# BMS.net
KiCad netlist of a schematic drawn in Altium Designer
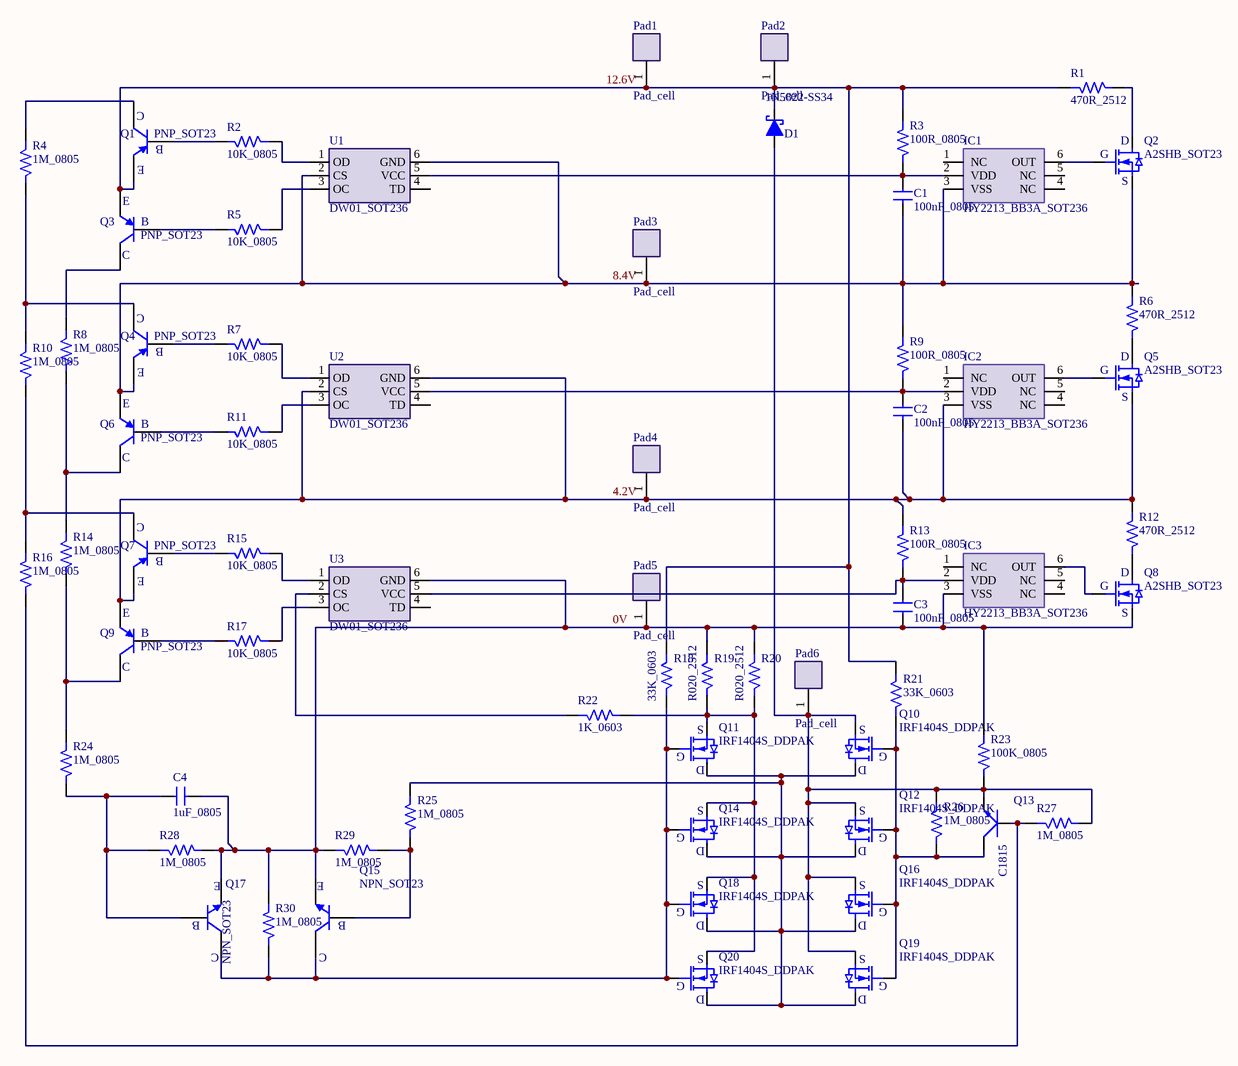
[diagram p0: BMS.SchDoc]

(export (version "E")
  (design (tool "Eeschema 10.0.6"))
  (components
    (comp (ref "C1")
      (value "100nF_0805")
      (footprint "CN-SMD-0805 - H32")
      (description "Cap SMD, 0.08x0.05 inch, 2.0x1.2 mm - 2012")
      (libsource (lib "LYAM_LIB") (part "CAP 0805 104"))
    )
    (comp (ref "C2")
      (value "100nF_0805")
      (footprint "CN-SMD-0805 - H32")
      (description "Cap SMD, 0.08x0.05 inch, 2.0x1.2 mm - 2012")
      (libsource (lib "LYAM_LIB") (part "CAP 0805 104"))
    )
    (comp (ref "C3")
      (value "100nF_0805")
      (footprint "CN-SMD-0805 - H32")
      (description "Cap SMD, 0.08x0.05 inch, 2.0x1.2 mm - 2012")
      (libsource (lib "LYAM_LIB") (part "CAP 0805 104"))
    )
    (comp (ref "C4")
      (value "1uF_0805")
      (footprint "CN-SMD-0805 - H50")
      (description "Cap SMD, 0.08x0.05 inch, 2.0x1.2 mm - 2012")
      (libsource (lib "LYAM_LIB") (part "CAP 0805 105"))
    )
    (comp (ref "D1")
      (value "1N5822-SS34")
      (footprint "SMA")
      (description "Schottky diode, 3A, VRRM 40V")
      (fields (field (name "PUBLISHER") "Altium Limited"))
      (libsource (lib "LYAM_LIB") (part "Diode 1N5822 SS34"))
    )
    (comp (ref "IC1")
      (value "HY2213_BB3A_SOT236")
      (footprint "SOT23-6")
      (description "1  Cell  Li-ion/Polymer  Battery  Charge  Balance  IC")
      (libsource (lib "LYAM_LIB") (part "HY2213"))
    )
    (comp (ref "IC2")
      (value "HY2213_BB3A_SOT236")
      (footprint "SOT23-6")
      (description "1  Cell  Li-ion/Polymer  Battery  Charge  Balance  IC")
      (libsource (lib "LYAM_LIB") (part "HY2213"))
    )
    (comp (ref "IC3")
      (value "HY2213_BB3A_SOT236")
      (footprint "SOT23-6")
      (description "1  Cell  Li-ion/Polymer  Battery  Charge  Balance  IC")
      (libsource (lib "LYAM_LIB") (part "HY2213"))
    )
    (comp (ref "Pad1")
      (value "Pad_cell")
      (footprint "Pad_cell")
      (libsource (lib "LYAM_LIB") (part "Pad_cell"))
    )
    (comp (ref "Pad2")
      (value "Pad_cell")
      (footprint "Pad_cell")
      (libsource (lib "LYAM_LIB") (part "Pad_cell"))
    )
    (comp (ref "Pad3")
      (value "Pad_cell")
      (footprint "Pad_cell")
      (libsource (lib "LYAM_LIB") (part "Pad_cell"))
    )
    (comp (ref "Pad4")
      (value "Pad_cell")
      (footprint "Pad_cell")
      (libsource (lib "LYAM_LIB") (part "Pad_cell"))
    )
    (comp (ref "Pad5")
      (value "Pad_cell")
      (footprint "Pad_cell")
      (libsource (lib "LYAM_LIB") (part "Pad_cell"))
    )
    (comp (ref "Pad6")
      (value "Pad_cell")
      (footprint "Pad_cell")
      (libsource (lib "LYAM_LIB") (part "Pad_cell"))
    )
    (comp (ref "Q1")
      (value "PNP_SOT23")
      (footprint "SOT23_3")
      (description "Transistor SMD MMBT5401 PNP 150V - SOT23")
      (libsource (lib "LYAM_LIB") (part "MMBT5401"))
    )
    (comp (ref "Q2")
      (value "A2SHB_SOT23")
      (footprint "SOT-23-3L")
      (description "N-Channel\r\nEnhancement Mode\r\nField Effect Transistor")
      (libsource (lib "LYAM_LIB") (part "HNM2302ALB"))
    )
    (comp (ref "Q3")
      (value "PNP_SOT23")
      (footprint "SOT23_3")
      (description "Transistor SMD MMBT5401 PNP 150V - SOT23")
      (libsource (lib "LYAM_LIB") (part "MMBT5401"))
    )
    (comp (ref "Q4")
      (value "PNP_SOT23")
      (footprint "SOT23_3")
      (description "Transistor SMD MMBT5401 PNP 150V - SOT23")
      (libsource (lib "LYAM_LIB") (part "MMBT5401"))
    )
    (comp (ref "Q5")
      (value "A2SHB_SOT23")
      (footprint "SOT-23-3L")
      (description "N-Channel\r\nEnhancement Mode\r\nField Effect Transistor")
      (libsource (lib "LYAM_LIB") (part "HNM2302ALB"))
    )
    (comp (ref "Q6")
      (value "PNP_SOT23")
      (footprint "SOT23_3")
      (description "Transistor SMD MMBT5401 PNP 150V - SOT23")
      (libsource (lib "LYAM_LIB") (part "MMBT5401"))
    )
    (comp (ref "Q7")
      (value "PNP_SOT23")
      (footprint "SOT23_3")
      (description "Transistor SMD MMBT5401 PNP 150V - SOT23")
      (libsource (lib "LYAM_LIB") (part "MMBT5401"))
    )
    (comp (ref "Q8")
      (value "A2SHB_SOT23")
      (footprint "SOT-23-3L")
      (description "N-Channel\r\nEnhancement Mode\r\nField Effect Transistor")
      (libsource (lib "LYAM_LIB") (part "HNM2302ALB"))
    )
    (comp (ref "Q9")
      (value "PNP_SOT23")
      (footprint "SOT23_3")
      (description "Transistor SMD MMBT5401 PNP 150V - SOT23")
      (libsource (lib "LYAM_LIB") (part "MMBT5401"))
    )
    (comp (ref "Q10")
      (value "IRF1404S_DDPAK")
      (footprint "TO263-3_DDPAK")
      (description "IRF1404S TO263 MOSFET N-CH 162A 40V")
      (libsource (lib "LYAM_LIB") (part "IRF1404S"))
    )
    (comp (ref "Q11")
      (value "IRF1404S_DDPAK")
      (footprint "TO263-3_DDPAK")
      (description "IRF1404S TO263 MOSFET N-CH 162A 40V")
      (libsource (lib "LYAM_LIB") (part "IRF1404S"))
    )
    (comp (ref "Q12")
      (value "IRF1404S_DDPAK")
      (footprint "TO263-3_DDPAK")
      (description "IRF1404S TO263 MOSFET N-CH 162A 40V")
      (libsource (lib "LYAM_LIB") (part "IRF1404S"))
    )
    (comp (ref "Q13")
      (value "C1815")
      (footprint "SOT23B")
      (description "NPN 600mW, ECB")
      (libsource (lib "LYAM_LIB") (part "Transistor C1815"))
    )
    (comp (ref "Q14")
      (value "IRF1404S_DDPAK")
      (footprint "TO263-3_DDPAK")
      (description "IRF1404S TO263 MOSFET N-CH 162A 40V")
      (libsource (lib "LYAM_LIB") (part "IRF1404S"))
    )
    (comp (ref "Q15")
      (value "NPN_SOT23")
      (footprint "SOT23_3")
      (description "2N5551 MMBT5551 G1 NPN Transistor 0.6A 160V SOT-23")
      (libsource (lib "LYAM_LIB") (part "MMBT5551"))
    )
    (comp (ref "Q16")
      (value "IRF1404S_DDPAK")
      (footprint "TO263-3_DDPAK")
      (description "IRF1404S TO263 MOSFET N-CH 162A 40V")
      (libsource (lib "LYAM_LIB") (part "IRF1404S"))
    )
    (comp (ref "Q17")
      (value "NPN_SOT23")
      (footprint "SOT23_3")
      (description "2N5551 MMBT5551 G1 NPN Transistor 0.6A 160V SOT-23")
      (libsource (lib "LYAM_LIB") (part "MMBT5551"))
    )
    (comp (ref "Q18")
      (value "IRF1404S_DDPAK")
      (footprint "TO263-3_DDPAK")
      (description "IRF1404S TO263 MOSFET N-CH 162A 40V")
      (libsource (lib "LYAM_LIB") (part "IRF1404S"))
    )
    (comp (ref "Q19")
      (value "IRF1404S_DDPAK")
      (footprint "TO263-3_DDPAK")
      (description "IRF1404S TO263 MOSFET N-CH 162A 40V")
      (libsource (lib "LYAM_LIB") (part "IRF1404S"))
    )
    (comp (ref "Q20")
      (value "IRF1404S_DDPAK")
      (footprint "TO263-3_DDPAK")
      (description "IRF1404S TO263 MOSFET N-CH 162A 40V")
      (libsource (lib "LYAM_LIB") (part "IRF1404S"))
    )
    (comp (ref "R1")
      (value "470R_2512")
      (footprint "RES-SMD-2512")
      (description "Resistor SMD, 0.25x0.12 inch, 6.3x3.2 mm - 6332, 1W")
      (libsource (lib "LYAM_LIB") (part "RES 2512 470R"))
    )
    (comp (ref "R2")
      (value "10K_0805")
      (footprint "RES-SMD-0805")
      (description "Resistor SMD, 0.08x0.05 inch, 2.0x1.2 mm - 2012, 1/8W")
      (libsource (lib "LYAM_LIB") (part "RES 0805 10K"))
    )
    (comp (ref "R3")
      (value "100R_0805")
      (footprint "RES-SMD-0805")
      (description "Resistor SMD, 0.08x0.05 inch, 2.0x1.2 mm - 2012, 1/8W")
      (libsource (lib "LYAM_LIB") (part "RES 0805 100R"))
    )
    (comp (ref "R4")
      (value "1M_0805")
      (footprint "RES-SMD-0805")
      (description "Resistor SMD, 0.08x0.05 inch, 2.0x1.2 mm - 2012, 1/8W")
      (libsource (lib "LYAM_LIB") (part "RES 0805 1M"))
    )
    (comp (ref "R5")
      (value "10K_0805")
      (footprint "RES-SMD-0805")
      (description "Resistor SMD, 0.08x0.05 inch, 2.0x1.2 mm - 2012, 1/8W")
      (libsource (lib "LYAM_LIB") (part "RES 0805 10K"))
    )
    (comp (ref "R6")
      (value "470R_2512")
      (footprint "RES-SMD-2512")
      (description "Resistor SMD, 0.25x0.12 inch, 6.3x3.2 mm - 6332, 1W")
      (libsource (lib "LYAM_LIB") (part "RES 2512 470R"))
    )
    (comp (ref "R7")
      (value "10K_0805")
      (footprint "RES-SMD-0805")
      (description "Resistor SMD, 0.08x0.05 inch, 2.0x1.2 mm - 2012, 1/8W")
      (libsource (lib "LYAM_LIB") (part "RES 0805 10K"))
    )
    (comp (ref "R8")
      (value "1M_0805")
      (footprint "RES-SMD-0805")
      (description "Resistor SMD, 0.08x0.05 inch, 2.0x1.2 mm - 2012, 1/8W")
      (libsource (lib "LYAM_LIB") (part "RES 0805 1M"))
    )
    (comp (ref "R9")
      (value "100R_0805")
      (footprint "RES-SMD-0805")
      (description "Resistor SMD, 0.08x0.05 inch, 2.0x1.2 mm - 2012, 1/8W")
      (libsource (lib "LYAM_LIB") (part "RES 0805 100R"))
    )
    (comp (ref "R10")
      (value "1M_0805")
      (footprint "RES-SMD-0805")
      (description "Resistor SMD, 0.08x0.05 inch, 2.0x1.2 mm - 2012, 1/8W")
      (libsource (lib "LYAM_LIB") (part "RES 0805 1M"))
    )
    (comp (ref "R11")
      (value "10K_0805")
      (footprint "RES-SMD-0805")
      (description "Resistor SMD, 0.08x0.05 inch, 2.0x1.2 mm - 2012, 1/8W")
      (libsource (lib "LYAM_LIB") (part "RES 0805 10K"))
    )
    (comp (ref "R12")
      (value "470R_2512")
      (footprint "RES-SMD-2512")
      (description "Resistor SMD, 0.25x0.12 inch, 6.3x3.2 mm - 6332, 1W")
      (libsource (lib "LYAM_LIB") (part "RES 2512 470R"))
    )
    (comp (ref "R13")
      (value "100R_0805")
      (footprint "RES-SMD-0805")
      (description "Resistor SMD, 0.08x0.05 inch, 2.0x1.2 mm - 2012, 1/8W")
      (libsource (lib "LYAM_LIB") (part "RES 0805 100R"))
    )
    (comp (ref "R14")
      (value "1M_0805")
      (footprint "RES-SMD-0805")
      (description "Resistor SMD, 0.08x0.05 inch, 2.0x1.2 mm - 2012, 1/8W")
      (libsource (lib "LYAM_LIB") (part "RES 0805 1M"))
    )
    (comp (ref "R15")
      (value "10K_0805")
      (footprint "RES-SMD-0805")
      (description "Resistor SMD, 0.08x0.05 inch, 2.0x1.2 mm - 2012, 1/8W")
      (libsource (lib "LYAM_LIB") (part "RES 0805 10K"))
    )
    (comp (ref "R16")
      (value "1M_0805")
      (footprint "RES-SMD-0805")
      (description "Resistor SMD, 0.08x0.05 inch, 2.0x1.2 mm - 2012, 1/8W")
      (libsource (lib "LYAM_LIB") (part "RES 0805 1M"))
    )
    (comp (ref "R17")
      (value "10K_0805")
      (footprint "RES-SMD-0805")
      (description "Resistor SMD, 0.08x0.05 inch, 2.0x1.2 mm - 2012, 1/8W")
      (libsource (lib "LYAM_LIB") (part "RES 0805 10K"))
    )
    (comp (ref "R18")
      (value "33K_0603")
      (footprint "RES-SMD-0603")
      (description "Resistor SMD, 0.06x0.03 inch, 1.55x0.85 mm - 1608, 1/10W")
      (libsource (lib "LYAM_LIB") (part "RES 0603 33K"))
    )
    (comp (ref "R19")
      (value "R020_2512")
      (footprint "RES-SMD-2512")
      (description "Resistor SMD, 0.25x0.12 inch, 6.3x3.2 mm - 6332, 1W")
      (libsource (lib "LYAM_LIB") (part "RES 2512 0.02R"))
    )
    (comp (ref "R20")
      (value "R020_2512")
      (footprint "RES-SMD-2512")
      (description "Resistor SMD, 0.25x0.12 inch, 6.3x3.2 mm - 6332, 1W")
      (libsource (lib "LYAM_LIB") (part "RES 2512 0.02R"))
    )
    (comp (ref "R21")
      (value "33K_0603")
      (footprint "RES-SMD-0603")
      (description "Resistor SMD, 0.06x0.03 inch, 1.55x0.85 mm - 1608, 1/10W")
      (libsource (lib "LYAM_LIB") (part "RES 0603 33K"))
    )
    (comp (ref "R22")
      (value "1K_0603")
      (footprint "RES-SMD-0603")
      (description "Resistor SMD, 0.06x0.03 inch, 1.55x0.85 mm - 1608, 1/10W")
      (libsource (lib "LYAM_LIB") (part "RES 0603 1K"))
    )
    (comp (ref "R23")
      (value "100K_0805")
      (footprint "RES-SMD-0805")
      (description "Resistor SMD, 0.08x0.05 inch, 2.0x1.2 mm - 2012, 1/8W")
      (libsource (lib "LYAM_LIB") (part "RES 0805 100K"))
    )
    (comp (ref "R24")
      (value "1M_0805")
      (footprint "RES-SMD-0805")
      (description "Resistor SMD, 0.08x0.05 inch, 2.0x1.2 mm - 2012, 1/8W")
      (libsource (lib "LYAM_LIB") (part "RES 0805 1M"))
    )
    (comp (ref "R25")
      (value "1M_0805")
      (footprint "RES-SMD-0805")
      (description "Resistor SMD, 0.08x0.05 inch, 2.0x1.2 mm - 2012, 1/8W")
      (libsource (lib "LYAM_LIB") (part "RES 0805 1M"))
    )
    (comp (ref "R26")
      (value "1M_0805")
      (footprint "RES-SMD-0805")
      (description "Resistor SMD, 0.08x0.05 inch, 2.0x1.2 mm - 2012, 1/8W")
      (libsource (lib "LYAM_LIB") (part "RES 0805 1M"))
    )
    (comp (ref "R27")
      (value "1M_0805")
      (footprint "RES-SMD-0805")
      (description "Resistor SMD, 0.08x0.05 inch, 2.0x1.2 mm - 2012, 1/8W")
      (libsource (lib "LYAM_LIB") (part "RES 0805 1M"))
    )
    (comp (ref "R28")
      (value "1M_0805")
      (footprint "RES-SMD-0805")
      (description "Resistor SMD, 0.08x0.05 inch, 2.0x1.2 mm - 2012, 1/8W")
      (libsource (lib "LYAM_LIB") (part "RES 0805 1M"))
    )
    (comp (ref "R29")
      (value "1M_0805")
      (footprint "RES-SMD-0805")
      (description "Resistor SMD, 0.08x0.05 inch, 2.0x1.2 mm - 2012, 1/8W")
      (libsource (lib "LYAM_LIB") (part "RES 0805 1M"))
    )
    (comp (ref "R30")
      (value "1M_0805")
      (footprint "RES-SMD-0805")
      (description "Resistor SMD, 0.08x0.05 inch, 2.0x1.2 mm - 2012, 1/8W")
      (libsource (lib "LYAM_LIB") (part "RES 0805 1M"))
    )
    (comp (ref "U1")
      (value "DW01_SOT236")
      (footprint "SOT23-6")
      (description "One Cell Lithium-ion/Polymer Battery Protection IC")
      (libsource (lib "LYAM_LIB") (part "DW01"))
    )
    (comp (ref "U2")
      (value "DW01_SOT236")
      (footprint "SOT23-6")
      (description "One Cell Lithium-ion/Polymer Battery Protection IC")
      (libsource (lib "LYAM_LIB") (part "DW01"))
    )
    (comp (ref "U3")
      (value "DW01_SOT236")
      (footprint "SOT23-6")
      (description "One Cell Lithium-ion/Polymer Battery Protection IC")
      (libsource (lib "LYAM_LIB") (part "DW01"))
    )
  )
  (nets
    (net (code "1") (name "/0V") (class "Default")
      (node (ref "C3") (pin "1") (pinfunction "1_1") (pintype "passive"))
      (node (ref "C4") (pin "2") (pinfunction "2_2") (pintype "passive"))
      (node (ref "IC3") (pin "3") (pinfunction "VSS_3") (pintype "passive"))
      (node (ref "Pad5") (pin "1") (pinfunction "11_1") (pintype "passive"))
      (node (ref "Q15") (pin "2") (pinfunction "E_2") (pintype "passive"))
      (node (ref "Q17") (pin "2") (pinfunction "E_2") (pintype "passive"))
      (node (ref "Q8") (pin "3") (pinfunction "S_3") (pintype "passive"))
      (node (ref "R19") (pin "2") (pinfunction "2_2") (pintype "passive"))
      (node (ref "R20") (pin "2") (pinfunction "2_2") (pintype "passive"))
      (node (ref "R23") (pin "2") (pinfunction "2_2") (pintype "passive"))
      (node (ref "R28") (pin "1") (pinfunction "1_1") (pintype "passive"))
      (node (ref "R29") (pin "2") (pinfunction "2_2") (pintype "passive"))
      (node (ref "R30") (pin "2") (pinfunction "2_2") (pintype "passive"))
      (node (ref "U3") (pin "6") (pinfunction "GND_6") (pintype "passive"))
    )
    (net (code "2") (name "/4.2V") (class "Default")
      (node (ref "C2") (pin "1") (pinfunction "1_1") (pintype "passive"))
      (node (ref "IC2") (pin "3") (pinfunction "VSS_3") (pintype "passive"))
      (node (ref "Pad4") (pin "1") (pinfunction "11_1") (pintype "passive"))
      (node (ref "Q5") (pin "3") (pinfunction "S_3") (pintype "passive"))
      (node (ref "Q7") (pin "2") (pinfunction "E_2") (pintype "passive"))
      (node (ref "Q9") (pin "2") (pinfunction "E_2") (pintype "passive"))
      (node (ref "R12") (pin "2") (pinfunction "2_2") (pintype "passive"))
      (node (ref "R13") (pin "2") (pinfunction "2_2") (pintype "passive"))
      (node (ref "U2") (pin "2") (pinfunction "CS_2") (pintype "passive"))
      (node (ref "U2") (pin "6") (pinfunction "GND_6") (pintype "passive"))
    )
    (net (code "3") (name "/8.4V") (class "Default")
      (node (ref "C1") (pin "1") (pinfunction "1_1") (pintype "passive"))
      (node (ref "IC1") (pin "3") (pinfunction "VSS_3") (pintype "passive"))
      (node (ref "Pad3") (pin "1") (pinfunction "11_1") (pintype "passive"))
      (node (ref "Q2") (pin "3") (pinfunction "S_3") (pintype "passive"))
      (node (ref "Q4") (pin "2") (pinfunction "E_2") (pintype "passive"))
      (node (ref "Q6") (pin "2") (pinfunction "E_2") (pintype "passive"))
      (node (ref "R6") (pin "2") (pinfunction "2_2") (pintype "passive"))
      (node (ref "R9") (pin "2") (pinfunction "2_2") (pintype "passive"))
      (node (ref "U1") (pin "2") (pinfunction "CS_2") (pintype "passive"))
      (node (ref "U1") (pin "6") (pinfunction "GND_6") (pintype "passive"))
    )
    (net (code "4") (name "/12.6V") (class "Default")
      (node (ref "D1") (pin "2") (pinfunction "K_2") (pintype "passive"))
      (node (ref "Pad1") (pin "1") (pinfunction "11_1") (pintype "passive"))
      (node (ref "Pad2") (pin "1") (pinfunction "11_1") (pintype "passive"))
      (node (ref "Q1") (pin "2") (pinfunction "E_2") (pintype "passive"))
      (node (ref "Q3") (pin "2") (pinfunction "E_2") (pintype "passive"))
      (node (ref "R1") (pin "2") (pinfunction "2_2") (pintype "passive"))
      (node (ref "R18") (pin "2") (pinfunction "2_2") (pintype "passive"))
      (node (ref "R21") (pin "1") (pinfunction "1_1") (pintype "passive"))
      (node (ref "R3") (pin "2") (pinfunction "2_2") (pintype "passive"))
    )
    (net (code "5") (name "Net-(D1-A)") (class "Default")
      (node (ref "D1") (pin "1") (pinfunction "A_1") (pintype "passive"))
      (node (ref "Pad6") (pin "1") (pinfunction "11_1") (pintype "passive"))
      (node (ref "Q10") (pin "3") (pinfunction "S_3") (pintype "passive"))
      (node (ref "Q12") (pin "3") (pinfunction "S_3") (pintype "passive"))
      (node (ref "Q13") (pin "1") (pinfunction "E_1") (pintype "passive"))
      (node (ref "Q16") (pin "3") (pinfunction "S_3") (pintype "passive"))
      (node (ref "Q19") (pin "3") (pinfunction "S_3") (pintype "passive"))
      (node (ref "R23") (pin "1") (pinfunction "1_1") (pintype "passive"))
      (node (ref "R26") (pin "2") (pinfunction "2_2") (pintype "passive"))
      (node (ref "R27") (pin "1") (pinfunction "1_1") (pintype "passive"))
    )
    (net (code "6") (name "Net-(IC1-OUT)") (class "Default")
      (node (ref "IC1") (pin "6") (pinfunction "OUT_6") (pintype "passive"))
      (node (ref "Q2") (pin "1") (pinfunction "G_1") (pintype "passive"))
    )
    (net (code "7") (name "Net-(IC1-VDD)") (class "Default")
      (node (ref "C1") (pin "2") (pinfunction "2_2") (pintype "passive"))
      (node (ref "IC1") (pin "2") (pinfunction "VDD_2") (pintype "passive"))
      (node (ref "R3") (pin "1") (pinfunction "1_1") (pintype "passive"))
      (node (ref "U1") (pin "5") (pinfunction "VCC_5") (pintype "passive"))
    )
    (net (code "8") (name "Net-(IC2-OUT)") (class "Default")
      (node (ref "IC2") (pin "6") (pinfunction "OUT_6") (pintype "passive"))
      (node (ref "Q5") (pin "1") (pinfunction "G_1") (pintype "passive"))
    )
    (net (code "9") (name "Net-(IC2-VDD)") (class "Default")
      (node (ref "C2") (pin "2") (pinfunction "2_2") (pintype "passive"))
      (node (ref "IC2") (pin "2") (pinfunction "VDD_2") (pintype "passive"))
      (node (ref "R9") (pin "1") (pinfunction "1_1") (pintype "passive"))
      (node (ref "U2") (pin "5") (pinfunction "VCC_5") (pintype "passive"))
    )
    (net (code "10") (name "Net-(IC3-OUT)") (class "Default")
      (node (ref "IC3") (pin "6") (pinfunction "OUT_6") (pintype "passive"))
      (node (ref "Q8") (pin "1") (pinfunction "G_1") (pintype "passive"))
    )
    (net (code "11") (name "Net-(IC3-VDD)") (class "Default")
      (node (ref "C3") (pin "2") (pinfunction "2_2") (pintype "passive"))
      (node (ref "IC3") (pin "2") (pinfunction "VDD_2") (pintype "passive"))
      (node (ref "R13") (pin "1") (pinfunction "1_1") (pintype "passive"))
      (node (ref "U3") (pin "5") (pinfunction "VCC_5") (pintype "passive"))
    )
    (net (code "12") (name "Net-(Q1-B)") (class "Default")
      (node (ref "Q1") (pin "1") (pinfunction "B_1") (pintype "passive"))
      (node (ref "R2") (pin "1") (pinfunction "1_1") (pintype "passive"))
    )
    (net (code "13") (name "Net-(Q1-C)") (class "Default")
      (node (ref "Q1") (pin "3") (pinfunction "C_3") (pintype "passive"))
      (node (ref "R4") (pin "2") (pinfunction "2_2") (pintype "passive"))
    )
    (net (code "14") (name "Net-(Q2-D)") (class "Default")
      (node (ref "Q2") (pin "2") (pinfunction "D_2") (pintype "passive"))
      (node (ref "R1") (pin "1") (pinfunction "1_1") (pintype "passive"))
    )
    (net (code "15") (name "Net-(Q3-B)") (class "Default")
      (node (ref "Q3") (pin "1") (pinfunction "B_1") (pintype "passive"))
      (node (ref "R5") (pin "1") (pinfunction "1_1") (pintype "passive"))
    )
    (net (code "16") (name "Net-(Q3-C)") (class "Default")
      (node (ref "Q3") (pin "3") (pinfunction "C_3") (pintype "passive"))
      (node (ref "R8") (pin "2") (pinfunction "2_2") (pintype "passive"))
    )
    (net (code "17") (name "Net-(Q4-B)") (class "Default")
      (node (ref "Q4") (pin "1") (pinfunction "B_1") (pintype "passive"))
      (node (ref "R7") (pin "1") (pinfunction "1_1") (pintype "passive"))
    )
    (net (code "18") (name "Net-(Q4-C)") (class "Default")
      (node (ref "Q4") (pin "3") (pinfunction "C_3") (pintype "passive"))
      (node (ref "R10") (pin "2") (pinfunction "2_2") (pintype "passive"))
      (node (ref "R4") (pin "1") (pinfunction "1_1") (pintype "passive"))
    )
    (net (code "19") (name "Net-(Q5-D)") (class "Default")
      (node (ref "Q5") (pin "2") (pinfunction "D_2") (pintype "passive"))
      (node (ref "R6") (pin "1") (pinfunction "1_1") (pintype "passive"))
    )
    (net (code "20") (name "Net-(Q6-B)") (class "Default")
      (node (ref "Q6") (pin "1") (pinfunction "B_1") (pintype "passive"))
      (node (ref "R11") (pin "1") (pinfunction "1_1") (pintype "passive"))
    )
    (net (code "21") (name "Net-(Q6-C)") (class "Default")
      (node (ref "Q6") (pin "3") (pinfunction "C_3") (pintype "passive"))
      (node (ref "R14") (pin "2") (pinfunction "2_2") (pintype "passive"))
      (node (ref "R8") (pin "1") (pinfunction "1_1") (pintype "passive"))
    )
    (net (code "22") (name "Net-(Q7-B)") (class "Default")
      (node (ref "Q7") (pin "1") (pinfunction "B_1") (pintype "passive"))
      (node (ref "R15") (pin "1") (pinfunction "1_1") (pintype "passive"))
    )
    (net (code "23") (name "Net-(Q7-C)") (class "Default")
      (node (ref "Q7") (pin "3") (pinfunction "C_3") (pintype "passive"))
      (node (ref "R10") (pin "1") (pinfunction "1_1") (pintype "passive"))
      (node (ref "R16") (pin "2") (pinfunction "2_2") (pintype "passive"))
    )
    (net (code "24") (name "Net-(Q8-D)") (class "Default")
      (node (ref "Q8") (pin "2") (pinfunction "D_2") (pintype "passive"))
      (node (ref "R12") (pin "1") (pinfunction "1_1") (pintype "passive"))
    )
    (net (code "25") (name "Net-(Q9-B)") (class "Default")
      (node (ref "Q9") (pin "1") (pinfunction "B_1") (pintype "passive"))
      (node (ref "R17") (pin "1") (pinfunction "1_1") (pintype "passive"))
    )
    (net (code "26") (name "Net-(Q9-C)") (class "Default")
      (node (ref "Q9") (pin "3") (pinfunction "C_3") (pintype "passive"))
      (node (ref "R14") (pin "1") (pinfunction "1_1") (pintype "passive"))
      (node (ref "R24") (pin "2") (pinfunction "2_2") (pintype "passive"))
    )
    (net (code "27") (name "Net-(Q10-D)") (class "Default")
      (node (ref "Q10") (pin "2") (pinfunction "D_2") (pintype "passive"))
      (node (ref "Q11") (pin "2") (pinfunction "D_2") (pintype "passive"))
      (node (ref "Q12") (pin "2") (pinfunction "D_2") (pintype "passive"))
      (node (ref "Q14") (pin "2") (pinfunction "D_2") (pintype "passive"))
      (node (ref "Q16") (pin "2") (pinfunction "D_2") (pintype "passive"))
      (node (ref "Q18") (pin "2") (pinfunction "D_2") (pintype "passive"))
      (node (ref "Q19") (pin "2") (pinfunction "D_2") (pintype "passive"))
      (node (ref "Q20") (pin "2") (pinfunction "D_2") (pintype "passive"))
      (node (ref "R25") (pin "2") (pinfunction "2_2") (pintype "passive"))
    )
    (net (code "28") (name "Net-(Q10-G)") (class "Default")
      (node (ref "Q10") (pin "1") (pinfunction "G_1") (pintype "passive"))
      (node (ref "Q12") (pin "1") (pinfunction "G_1") (pintype "passive"))
      (node (ref "Q13") (pin "2") (pinfunction "C_2") (pintype "passive"))
      (node (ref "Q16") (pin "1") (pinfunction "G_1") (pintype "passive"))
      (node (ref "Q19") (pin "1") (pinfunction "G_1") (pintype "passive"))
      (node (ref "R21") (pin "2") (pinfunction "2_2") (pintype "passive"))
      (node (ref "R26") (pin "1") (pinfunction "1_1") (pintype "passive"))
    )
    (net (code "29") (name "Net-(Q11-G)") (class "Default")
      (node (ref "Q11") (pin "1") (pinfunction "G_1") (pintype "passive"))
      (node (ref "Q14") (pin "1") (pinfunction "G_1") (pintype "passive"))
      (node (ref "Q15") (pin "3") (pinfunction "C_3") (pintype "passive"))
      (node (ref "Q17") (pin "3") (pinfunction "C_3") (pintype "passive"))
      (node (ref "Q18") (pin "1") (pinfunction "G_1") (pintype "passive"))
      (node (ref "Q20") (pin "1") (pinfunction "G_1") (pintype "passive"))
      (node (ref "R18") (pin "1") (pinfunction "1_1") (pintype "passive"))
      (node (ref "R30") (pin "1") (pinfunction "1_1") (pintype "passive"))
    )
    (net (code "30") (name "Net-(Q11-S)") (class "Default")
      (node (ref "Q11") (pin "3") (pinfunction "S_3") (pintype "passive"))
      (node (ref "Q14") (pin "3") (pinfunction "S_3") (pintype "passive"))
      (node (ref "Q18") (pin "3") (pinfunction "S_3") (pintype "passive"))
      (node (ref "Q20") (pin "3") (pinfunction "S_3") (pintype "passive"))
      (node (ref "R19") (pin "1") (pinfunction "1_1") (pintype "passive"))
      (node (ref "R20") (pin "1") (pinfunction "1_1") (pintype "passive"))
      (node (ref "R22") (pin "1") (pinfunction "1_1") (pintype "passive"))
    )
    (net (code "31") (name "Net-(Q13-B)") (class "Default")
      (node (ref "Q13") (pin "3") (pinfunction "B_3") (pintype "passive"))
      (node (ref "R16") (pin "1") (pinfunction "1_1") (pintype "passive"))
      (node (ref "R27") (pin "2") (pinfunction "2_2") (pintype "passive"))
    )
    (net (code "32") (name "Net-(Q15-B)") (class "Default")
      (node (ref "Q15") (pin "1") (pinfunction "B_1") (pintype "passive"))
      (node (ref "R25") (pin "1") (pinfunction "1_1") (pintype "passive"))
      (node (ref "R29") (pin "1") (pinfunction "1_1") (pintype "passive"))
    )
    (net (code "33") (name "Net-(Q17-B)") (class "Default")
      (node (ref "C4") (pin "1") (pinfunction "1_1") (pintype "passive"))
      (node (ref "Q17") (pin "1") (pinfunction "B_1") (pintype "passive"))
      (node (ref "R24") (pin "1") (pinfunction "1_1") (pintype "passive"))
      (node (ref "R28") (pin "2") (pinfunction "2_2") (pintype "passive"))
    )
    (net (code "34") (name "Net-(U1-OC)") (class "Default")
      (node (ref "R5") (pin "2") (pinfunction "2_2") (pintype "passive"))
      (node (ref "U1") (pin "3") (pinfunction "OC_3") (pintype "passive"))
    )
    (net (code "35") (name "Net-(U1-OD)") (class "Default")
      (node (ref "R2") (pin "2") (pinfunction "2_2") (pintype "passive"))
      (node (ref "U1") (pin "1") (pinfunction "OD_1") (pintype "passive"))
    )
    (net (code "36") (name "Net-(U2-OC)") (class "Default")
      (node (ref "R11") (pin "2") (pinfunction "2_2") (pintype "passive"))
      (node (ref "U2") (pin "3") (pinfunction "OC_3") (pintype "passive"))
    )
    (net (code "37") (name "Net-(U2-OD)") (class "Default")
      (node (ref "R7") (pin "2") (pinfunction "2_2") (pintype "passive"))
      (node (ref "U2") (pin "1") (pinfunction "OD_1") (pintype "passive"))
    )
    (net (code "38") (name "Net-(U3-CS)") (class "Default")
      (node (ref "R22") (pin "2") (pinfunction "2_2") (pintype "passive"))
      (node (ref "U3") (pin "2") (pinfunction "CS_2") (pintype "passive"))
    )
    (net (code "39") (name "Net-(U3-OC)") (class "Default")
      (node (ref "R17") (pin "2") (pinfunction "2_2") (pintype "passive"))
      (node (ref "U3") (pin "3") (pinfunction "OC_3") (pintype "passive"))
    )
    (net (code "40") (name "Net-(U3-OD)") (class "Default")
      (node (ref "R15") (pin "2") (pinfunction "2_2") (pintype "passive"))
      (node (ref "U3") (pin "1") (pinfunction "OD_1") (pintype "passive"))
    )
    (net (code "41") (name "unconnected-(IC1-NC-Pad1)") (class "Default")
      (node (ref "IC1") (pin "1") (pinfunction "NC_1") (pintype "passive"))
    )
    (net (code "42") (name "unconnected-(IC1-NC-Pad4)") (class "Default")
      (node (ref "IC1") (pin "4") (pinfunction "NC_4") (pintype "passive"))
    )
    (net (code "43") (name "unconnected-(IC1-NC-Pad5)") (class "Default")
      (node (ref "IC1") (pin "5") (pinfunction "NC_5") (pintype "passive"))
    )
    (net (code "44") (name "unconnected-(IC2-NC-Pad1)") (class "Default")
      (node (ref "IC2") (pin "1") (pinfunction "NC_1") (pintype "passive"))
    )
    (net (code "45") (name "unconnected-(IC2-NC-Pad4)") (class "Default")
      (node (ref "IC2") (pin "4") (pinfunction "NC_4") (pintype "passive"))
    )
    (net (code "46") (name "unconnected-(IC2-NC-Pad5)") (class "Default")
      (node (ref "IC2") (pin "5") (pinfunction "NC_5") (pintype "passive"))
    )
    (net (code "47") (name "unconnected-(IC3-NC-Pad1)") (class "Default")
      (node (ref "IC3") (pin "1") (pinfunction "NC_1") (pintype "passive"))
    )
    (net (code "48") (name "unconnected-(IC3-NC-Pad4)") (class "Default")
      (node (ref "IC3") (pin "4") (pinfunction "NC_4") (pintype "passive"))
    )
    (net (code "49") (name "unconnected-(IC3-NC-Pad5)") (class "Default")
      (node (ref "IC3") (pin "5") (pinfunction "NC_5") (pintype "passive"))
    )
    (net (code "50") (name "unconnected-(U1-TD-Pad4)") (class "Default")
      (node (ref "U1") (pin "4") (pinfunction "TD_4") (pintype "passive"))
    )
    (net (code "51") (name "unconnected-(U2-TD-Pad4)") (class "Default")
      (node (ref "U2") (pin "4") (pinfunction "TD_4") (pintype "passive"))
    )
    (net (code "52") (name "unconnected-(U3-TD-Pad4)") (class "Default")
      (node (ref "U3") (pin "4") (pinfunction "TD_4") (pintype "passive"))
    )
  )
)
